# SH7_-_CAN.net
KiCad netlist of a schematic drawn in Altium Designer
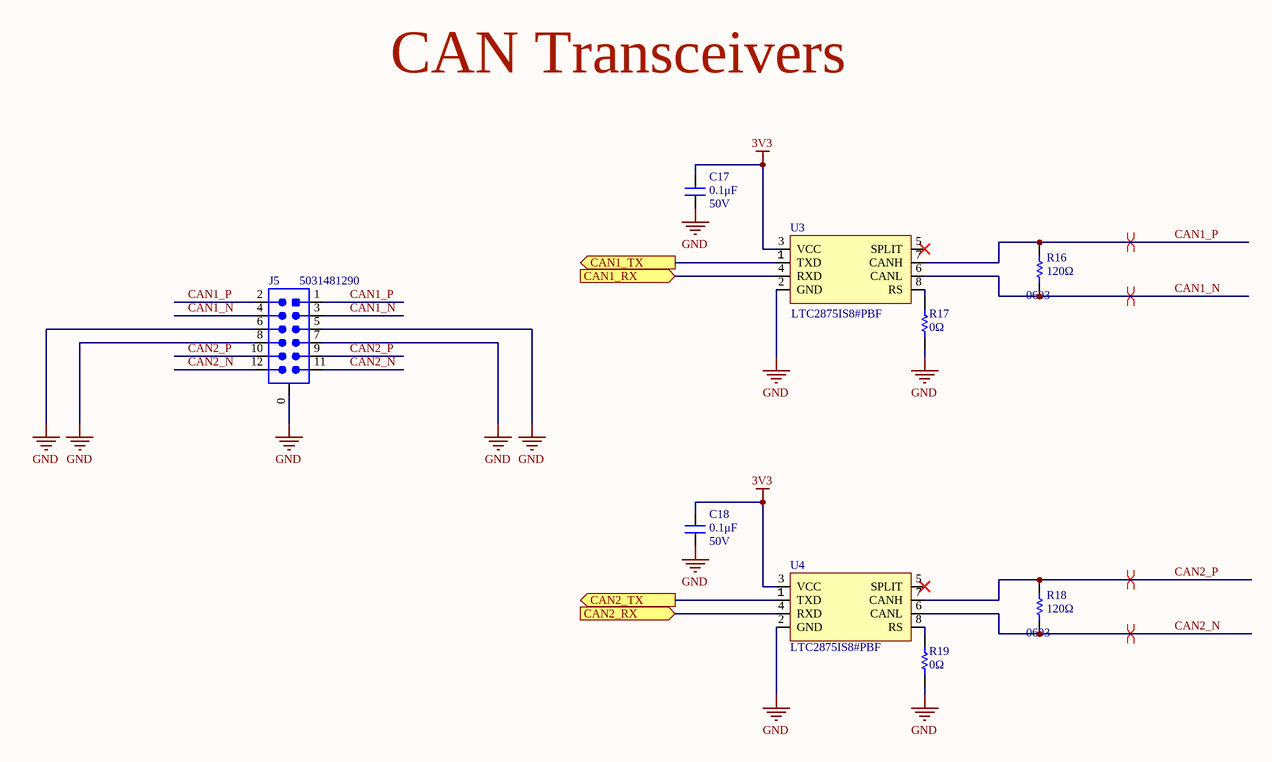
[diagram p0: SH7 - CAN.SchDoc]

(export (version "E")
  (design (tool "Eeschema 10.0.6"))
  (components
    (comp (ref "C17")
      (value "0.1μF")
      (footprint "CAP0603")
      (description "CAP CER 0.1UF 50V X7R 0603")
      (fields (field (name "VOLTAGE RATING") "50V") (field (name "Comment") "CAP_0.1uF_50V_0603"))
      (libsource (lib "UWRT_Schematic_Library_2020") (part "CAP_0.1uF_50V_0603"))
    )
    (comp (ref "C18")
      (value "0.1μF")
      (footprint "CAP0603")
      (description "CAP CER 0.1UF 50V X7R 0603")
      (fields (field (name "VOLTAGE RATING") "50V") (field (name "Comment") "CAP_0.1uF_50V_0603"))
      (libsource (lib "UWRT_Schematic_Library_2020") (part "CAP_0.1uF_50V_0603"))
    )
    (comp (ref "J5")
      (value "CON_6x2M_SM_RA")
      (footprint "MOLEX-5031481290")
      (description "CONN HEADER SMD RIGHT ANGLE 1.5MM PITCH")
      (fields (field (name "MANUFACTURER PART NUMBER 1") "5031481290"))
      (libsource (lib "UWRT_Schematic_Library_2020") (part "CON_6x2M_SM_RA"))
    )
    (comp (ref "R16")
      (value "RES_120Ω_0603_5%_HP")
      (footprint "RESC0603")
      (description "RES 120 OHM 5% 1/4W 0603")
      (fields
        (field (name "TOLERANCE") "5%")
        (field (name "RESISTANCE") "120Ω")
        (field (name "PACKAGE/FOOTPRINT") "0603")
      )
      (libsource (lib "UWRT_Schematic_Library_2020") (part "RES_120Ω_0603_5%_HP"))
    )
    (comp (ref "R17")
      (value "0Ω")
      (footprint "RESC0603")
      (description "RES 0 OHM JUMPER 1/10W 0603")
      (fields (field (name "Comment") "RES_0Ω_0603"))
      (libsource (lib "UWRT_Schematic_Library_2020") (part "RES_0Ω_0603"))
    )
    (comp (ref "R18")
      (value "RES_120Ω_0603_5%_HP")
      (footprint "RESC0603")
      (description "RES 120 OHM 5% 1/4W 0603")
      (fields
        (field (name "TOLERANCE") "5%")
        (field (name "RESISTANCE") "120Ω")
        (field (name "PACKAGE/FOOTPRINT") "0603")
      )
      (libsource (lib "UWRT_Schematic_Library_2020") (part "RES_120Ω_0603_5%_HP"))
    )
    (comp (ref "R19")
      (value "0Ω")
      (footprint "RESC0603")
      (description "RES 0 OHM JUMPER 1/10W 0603")
      (fields (field (name "Comment") "RES_0Ω_0603"))
      (libsource (lib "UWRT_Schematic_Library_2020") (part "RES_0Ω_0603"))
    )
    (comp (ref "U3")
      (value "LTC2875")
      (footprint "LT-S8_N")
      (description "IC TXRX CAN 4MBPS 8SO")
      (fields
        (field (name "MANUFACTURER PART NUMBER 1") "LTC2875IS8#PBF")
        (field (name "LCSC PART #") "C117076")
      )
      (libsource (lib "UWRT_Schematic_Library_2020") (part "LTC2875"))
    )
    (comp (ref "U4")
      (value "LTC2875")
      (footprint "LT-S8_N")
      (description "IC TXRX CAN 4MBPS 8SO")
      (fields
        (field (name "MANUFACTURER PART NUMBER 1") "LTC2875IS8#PBF")
        (field (name "LCSC PART #") "C117076")
      )
      (libsource (lib "UWRT_Schematic_Library_2020") (part "LTC2875"))
    )
  )
  (nets
    (net (code "1") (name "/CAN1_N") (class "Default")
      (node (ref "J5") (pin "3") (pinfunction "3_3") (pintype "passive"))
      (node (ref "J5") (pin "4") (pinfunction "4_4") (pintype "passive"))
      (node (ref "R16") (pin "1") (pinfunction "1_1") (pintype "passive"))
      (node (ref "U3") (pin "6") (pinfunction "CANL_6") (pintype "passive"))
    )
    (net (code "2") (name "/CAN1_P") (class "Default")
      (node (ref "J5") (pin "1") (pinfunction "1_1") (pintype "passive"))
      (node (ref "J5") (pin "2") (pinfunction "2_2") (pintype "passive"))
      (node (ref "R16") (pin "2") (pinfunction "2_2") (pintype "passive"))
      (node (ref "U3") (pin "7") (pinfunction "CANH_7") (pintype "passive"))
    )
    (net (code "3") (name "/CAN1_RX") (class "Default")
      (node (ref "U3") (pin "4") (pinfunction "RXD_4") (pintype "passive"))
    )
    (net (code "4") (name "/CAN1_TX") (class "Default")
      (node (ref "U3") (pin "1") (pinfunction "TXD_1") (pintype "passive"))
    )
    (net (code "5") (name "/CAN2_N") (class "Default")
      (node (ref "J5") (pin "11") (pinfunction "11_11") (pintype "passive"))
      (node (ref "J5") (pin "12") (pinfunction "12_12") (pintype "passive"))
      (node (ref "R18") (pin "1") (pinfunction "1_1") (pintype "passive"))
      (node (ref "U4") (pin "6") (pinfunction "CANL_6") (pintype "passive"))
    )
    (net (code "6") (name "/CAN2_P") (class "Default")
      (node (ref "J5") (pin "10") (pinfunction "10_10") (pintype "passive"))
      (node (ref "J5") (pin "9") (pinfunction "9_9") (pintype "passive"))
      (node (ref "R18") (pin "2") (pinfunction "2_2") (pintype "passive"))
      (node (ref "U4") (pin "7") (pinfunction "CANH_7") (pintype "passive"))
    )
    (net (code "7") (name "/CAN2_RX") (class "Default")
      (node (ref "U4") (pin "4") (pinfunction "RXD_4") (pintype "passive"))
    )
    (net (code "8") (name "/CAN2_TX") (class "Default")
      (node (ref "U4") (pin "1") (pinfunction "TXD_1") (pintype "passive"))
    )
    (net (code "9") (name "3V3") (class "Default")
      (node (ref "C17") (pin "1") (pinfunction "1_1") (pintype "passive"))
      (node (ref "C18") (pin "1") (pinfunction "1_1") (pintype "passive"))
      (node (ref "U3") (pin "3") (pinfunction "VCC_3") (pintype "passive"))
      (node (ref "U4") (pin "3") (pinfunction "VCC_3") (pintype "passive"))
    )
    (net (code "10") (name "GND") (class "Default")
      (node (ref "C17") (pin "2") (pinfunction "2_2") (pintype "passive"))
      (node (ref "C18") (pin "2") (pinfunction "2_2") (pintype "passive"))
      (node (ref "J5") (pin "0") (pinfunction "0_0") (pintype "passive"))
      (node (ref "J5") (pin "5") (pinfunction "5_5") (pintype "passive"))
      (node (ref "J5") (pin "6") (pinfunction "6_6") (pintype "passive"))
      (node (ref "J5") (pin "7") (pinfunction "7_7") (pintype "passive"))
      (node (ref "J5") (pin "8") (pinfunction "8_8") (pintype "passive"))
      (node (ref "R17") (pin "1") (pinfunction "1_1") (pintype "passive"))
      (node (ref "R19") (pin "1") (pinfunction "1_1") (pintype "passive"))
      (node (ref "U3") (pin "2") (pinfunction "GND_2") (pintype "passive"))
      (node (ref "U4") (pin "2") (pinfunction "GND_2") (pintype "passive"))
    )
    (net (code "11") (name "Net-(U3-RS)") (class "Default")
      (node (ref "R17") (pin "2") (pinfunction "2_2") (pintype "passive"))
      (node (ref "U3") (pin "8") (pinfunction "RS_8") (pintype "passive"))
    )
    (net (code "12") (name "Net-(U4-RS)") (class "Default")
      (node (ref "R19") (pin "2") (pinfunction "2_2") (pintype "passive"))
      (node (ref "U4") (pin "8") (pinfunction "RS_8") (pintype "passive"))
    )
    (net (code "13") (name "unconnected-(U3-SPLIT-Pad5)") (class "Default")
      (node (ref "U3") (pin "5") (pinfunction "SPLIT_5") (pintype "passive+no_connect"))
    )
    (net (code "14") (name "unconnected-(U4-SPLIT-Pad5)") (class "Default")
      (node (ref "U4") (pin "5") (pinfunction "SPLIT_5") (pintype "passive+no_connect"))
    )
  )
)
